# Sheet1.net
KiCad netlist of a schematic drawn in Altium Designer
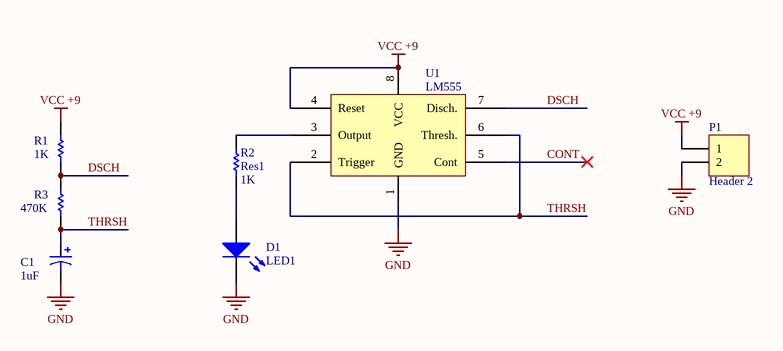
[diagram p0: Sheet1.SchDoc]

(export (version "E")
  (design (tool "Eeschema 10.0.6"))
  (components
    (comp (ref "C1")
      (value "1uF")
      (footprint "RB7.6-15")
      (description "Polarized Capacitor (Radial)")
      (fields (field (name "Comment") "Cap Pol1") (field (name "PUBLISHER") "Altium Limited"))
      (libsource (lib "Miscellaneous Devices") (part "Cap Pol1"))
    )
    (comp (ref "D1")
      (value "LED1")
      (footprint "LED-1")
      (description "Typical RED GaAs LED")
      (fields (field (name "PUBLISHER") "Altium Limited"))
      (libsource (lib "Miscellaneous Devices") (part "LED1"))
    )
    (comp (ref "P1")
      (value "Header 2")
      (footprint "HDR1X2")
      (description "Header, 2-Pin")
      (fields (field (name "PUBLISHER") "Altium Limited"))
      (libsource (lib "Miscellaneous Connectors") (part "Header 2"))
    )
    (comp (ref "R1")
      (value "1K")
      (footprint "AXIAL-0.3")
      (description "Resistor")
      (fields (field (name "Comment") "Res1") (field (name "PUBLISHER") "Altium Limited"))
      (libsource (lib "Miscellaneous Devices") (part "Res1"))
    )
    (comp (ref "R2")
      (value "Res1")
      (footprint "AXIAL-0.3")
      (description "Resistor")
      (fields (field (name "ALTIUM_VALUE") "1K") (field (name "PUBLISHER") "Altium Limited"))
      (libsource (lib "Miscellaneous Devices") (part "Res1"))
    )
    (comp (ref "R3")
      (value "470K")
      (footprint "AXIAL-0.3")
      (description "Resistor")
      (fields (field (name "Comment") "Res1") (field (name "PUBLISHER") "Altium Limited"))
      (libsource (lib "Miscellaneous Devices") (part "Res1"))
    )
    (comp (ref "U1")
      (value "LM555")
      (footprint "LM555DIP")
      (description "LM555 Timer DIP IC")
      (libsource (lib "Schlib1") (part "LM555"))
    )
  )
  (nets
    (net (code "1") (name "/CONT") (class "Default")
      (node (ref "U1") (pin "5") (pinfunction "Cont_5") (pintype "passive+no_connect"))
    )
    (net (code "2") (name "/DSCH") (class "Default")
      (node (ref "R1") (pin "1") (pinfunction "1_1") (pintype "passive"))
      (node (ref "R3") (pin "2") (pinfunction "2_2") (pintype "passive"))
      (node (ref "U1") (pin "7") (pinfunction "Disch._7") (pintype "passive"))
    )
    (net (code "3") (name "/THRSH") (class "Default")
      (node (ref "C1") (pin "1") (pinfunction "1_1") (pintype "passive"))
      (node (ref "R3") (pin "1") (pinfunction "1_1") (pintype "passive"))
      (node (ref "U1") (pin "2") (pinfunction "Trigger_2") (pintype "passive"))
      (node (ref "U1") (pin "6") (pinfunction "Thresh._6") (pintype "passive"))
    )
    (net (code "4") (name "GND") (class "Default")
      (node (ref "C1") (pin "2") (pinfunction "2_2") (pintype "passive"))
      (node (ref "D1") (pin "2") (pinfunction "K_2") (pintype "passive"))
      (node (ref "P1") (pin "2") (pinfunction "2_2") (pintype "passive"))
      (node (ref "U1") (pin "1") (pinfunction "GND_1") (pintype "passive"))
    )
    (net (code "5") (name "Net-(D1-A)") (class "Default")
      (node (ref "D1") (pin "1") (pinfunction "A_1") (pintype "passive"))
      (node (ref "R2") (pin "1") (pinfunction "1_1") (pintype "passive"))
    )
    (net (code "6") (name "Net-(U1-Output)") (class "Default")
      (node (ref "R2") (pin "2") (pinfunction "2_2") (pintype "passive"))
      (node (ref "U1") (pin "3") (pinfunction "Output_3") (pintype "passive"))
    )
    (net (code "7") (name "VCC +9") (class "Default")
      (node (ref "P1") (pin "1") (pinfunction "1_1") (pintype "passive"))
      (node (ref "R1") (pin "2") (pinfunction "2_2") (pintype "passive"))
      (node (ref "U1") (pin "4") (pinfunction "Reset_4") (pintype "passive"))
      (node (ref "U1") (pin "8") (pinfunction "VCC_8") (pintype "passive"))
    )
  )
)
